# power_3_4v.net
KiCad netlist of a schematic drawn in EAGLE
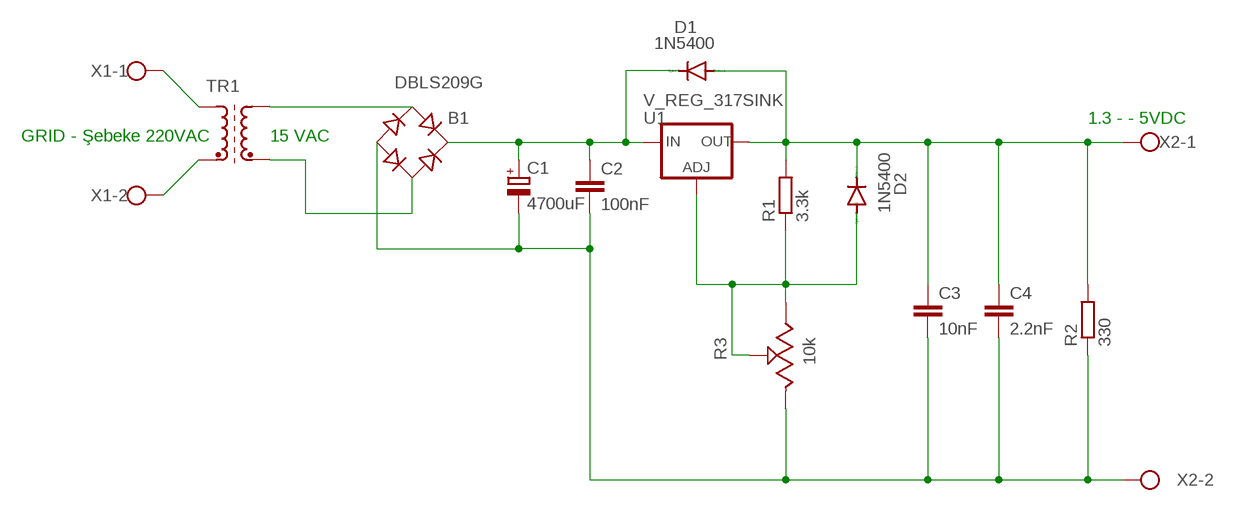
[diagram p0: schematic, sheet 1]

(export (version "E")
  (design (tool "Eeschema 10.0.6"))
  (components
    (comp (ref "B1")
      (value "DBLS209G")
      (footprint "eagle-import:DBS")
      (libsource (lib "eagle-import") (part "DB?GLS209"))
    )
    (comp (ref "C1")
      (value "4700uF")
      (footprint "eagle-import:140CLH-1010")
      (libsource (lib "eagle-import") (part "CPOL-EU140CLH-1010"))
    )
    (comp (ref "C2")
      (value "100nF")
      (footprint "eagle-import:C025-025X050")
      (libsource (lib "eagle-import") (part "C-EU025-025X050"))
    )
    (comp (ref "C3")
      (value "10nF")
      (footprint "eagle-import:C025-025X050")
      (libsource (lib "eagle-import") (part "C-EU025-025X050"))
    )
    (comp (ref "C4")
      (value "2.2nF")
      (footprint "eagle-import:C025-025X050")
      (libsource (lib "eagle-import") (part "C-EU025-025X050"))
    )
    (comp (ref "D1")
      (value "1N5400")
      (footprint "eagle-import:DO201-15")
      (libsource (lib "eagle-import") (part "1N5400"))
    )
    (comp (ref "D2")
      (value "1N5400")
      (footprint "eagle-import:DO201-15")
      (libsource (lib "eagle-import") (part "1N5400"))
    )
    (comp (ref "R1")
      (value "3.3k")
      (footprint "eagle-import:0204_7")
      (libsource (lib "eagle-import") (part "R-EU_0204/7"))
    )
    (comp (ref "R2")
      (value "330")
      (footprint "eagle-import:0204_7")
      (libsource (lib "eagle-import") (part "R-EU_0204/7"))
    )
    (comp (ref "R3")
      (value "10k")
      (footprint "eagle-import:3310C-001-503L")
      (fields
        (field (name "DIGIKEY_PARTNO") "3310C-001-503L-ND")
        (field (name "MANUFACTURER") "Bourns Inc.")
        (field (name "MPN") "3310C-001-503L")
        (field (name "CREATED_BY") "PCBLayout.com")
      )
      (libsource (lib "eagle-import") (part "3310C-001-503L"))
    )
    (comp (ref "TR1")
      (value "SM-T4")
      (footprint "eagle-import:SM-T4")
      (libsource (lib "eagle-import") (part "SM-T4"))
    )
    (comp (ref "U1")
      (value "V_REG_317SINK")
      (footprint "eagle-import:TO220-ADJ")
      (libsource (lib "eagle-import") (part "V_REG_317SINK"))
    )
    (comp (ref "X1")
      (value "W237-102")
      (footprint "eagle-import:W237-102")
      (fields (field (name "MPN") "237-102"))
      (libsource (lib "eagle-import") (part "W237-102"))
    )
    (comp (ref "X2")
      (value "W237-102")
      (footprint "eagle-import:W237-102")
      (fields (field (name "MPN") "237-102"))
      (libsource (lib "eagle-import") (part "W237-102"))
    )
  )
  (nets
    (net (code "1") (name "Net-(B1-Pad+)") (class "Default")
      (node (ref "B1") (pin "+") (pinfunction "+_+") (pintype "passive"))
      (node (ref "C1") (pin "+") (pinfunction "+_+") (pintype "passive"))
      (node (ref "C2") (pin "1") (pinfunction "1_1") (pintype "passive"))
      (node (ref "D1") (pin "C") (pinfunction "C_C") (pintype "passive"))
      (node (ref "U1") (pin "IN") (pinfunction "IN_IN") (pintype "input"))
    )
    (net (code "2") (name "Net-(D2-PadA)") (class "Default")
      (node (ref "D2") (pin "A") (pinfunction "A_A") (pintype "passive"))
      (node (ref "R1") (pin "1") (pinfunction "1_1") (pintype "passive"))
      (node (ref "R3") (pin "2") (pinfunction "2_2") (pintype "passive"))
      (node (ref "R3") (pin "3") (pinfunction "3_3") (pintype "passive"))
      (node (ref "U1") (pin "ADJ") (pinfunction "ADJ_ADJ") (pintype "input"))
    )
    (net (code "3") (name "Net-(TR1-A1)") (class "Default")
      (node (ref "TR1") (pin "1") (pinfunction "A1_1") (pintype "passive"))
      (node (ref "X1") (pin "1") (pinfunction "KL_1") (pintype "passive"))
    )
    (net (code "4") (name "Net-(TR1-A2)") (class "Default")
      (node (ref "B1") (pin "AC1") (pinfunction "AC1_AC1") (pintype "passive"))
      (node (ref "TR1") (pin "5") (pinfunction "A2_5") (pintype "passive"))
    )
    (net (code "5") (name "Net-(TR1-E1)") (class "Default")
      (node (ref "TR1") (pin "2") (pinfunction "E1_2") (pintype "passive"))
      (node (ref "X1") (pin "2") (pinfunction "KL_2") (pintype "passive"))
    )
    (net (code "6") (name "Net-(TR1-E2)") (class "Default")
      (node (ref "B1") (pin "AC2") (pinfunction "AC2_AC2") (pintype "passive"))
      (node (ref "TR1") (pin "4") (pinfunction "E2_4") (pintype "passive"))
    )
    (net (code "7") (name "Net-(X2A-KL)") (class "Default")
      (node (ref "C3") (pin "1") (pinfunction "1_1") (pintype "passive"))
      (node (ref "C4") (pin "1") (pinfunction "1_1") (pintype "passive"))
      (node (ref "D1") (pin "A") (pinfunction "A_A") (pintype "passive"))
      (node (ref "D2") (pin "C") (pinfunction "C_C") (pintype "passive"))
      (node (ref "R1") (pin "2") (pinfunction "2_2") (pintype "passive"))
      (node (ref "R2") (pin "2") (pinfunction "2_2") (pintype "passive"))
      (node (ref "U1") (pin "OUT") (pinfunction "OUT_OUT") (pintype "output"))
      (node (ref "X2") (pin "1") (pinfunction "KL_1") (pintype "passive"))
    )
    (net (code "8") (name "Net-(X2B-KL)") (class "Default")
      (node (ref "B1") (pin "-") (pinfunction "-_-") (pintype "passive"))
      (node (ref "C1") (pin "-") (pinfunction "-_-") (pintype "passive"))
      (node (ref "C2") (pin "2") (pinfunction "2_2") (pintype "passive"))
      (node (ref "C3") (pin "2") (pinfunction "2_2") (pintype "passive"))
      (node (ref "C4") (pin "2") (pinfunction "2_2") (pintype "passive"))
      (node (ref "R2") (pin "1") (pinfunction "1_1") (pintype "passive"))
      (node (ref "R3") (pin "1") (pinfunction "1_1") (pintype "passive"))
      (node (ref "X2") (pin "2") (pinfunction "KL_2") (pintype "passive"))
    )
  )
)
